# Trd_pcb.net
KiCad netlist of a schematic drawn in EAGLE
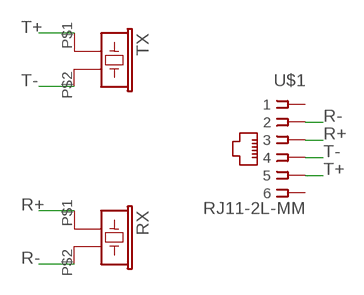
[diagram p0: schematic, sheet 1]

(export (version "E")
  (design (tool "Eeschema 10.0.6"))
  (components
    (comp (ref "RX")
      (value "400ST/R100")
      (footprint "eagle-import:DIA-9.7-5")
      (libsource (lib "eagle-import") (part "400ST/R100"))
    )
    (comp (ref "TX")
      (value "400ST/R100")
      (footprint "eagle-import:DIA-9.7-5")
      (libsource (lib "eagle-import") (part "400ST/R100"))
    )
    (comp (ref "U$1")
      (value "RJ11-2L-MM")
      (footprint "eagle-import:RJ11-NO_SHIELD_2")
      (libsource (lib "eagle-import") (part "RJ11-2L-MM"))
    )
  )
  (nets
    (net (code "1") (name "/R+") (class "Default")
      (node (ref "RX") (pin "P$1") (pinfunction "1_P$1") (pintype "passive"))
      (node (ref "U$1") (pin "3") (pinfunction "3_3") (pintype "passive"))
    )
    (net (code "2") (name "/R-") (class "Default")
      (node (ref "RX") (pin "P$2") (pinfunction "2_P$2") (pintype "passive"))
      (node (ref "U$1") (pin "2") (pinfunction "2_2") (pintype "passive"))
    )
    (net (code "3") (name "/T+") (class "Default")
      (node (ref "TX") (pin "P$1") (pinfunction "1_P$1") (pintype "passive"))
      (node (ref "U$1") (pin "5") (pinfunction "5_5") (pintype "passive"))
    )
    (net (code "4") (name "/T-") (class "Default")
      (node (ref "TX") (pin "P$2") (pinfunction "2_P$2") (pintype "passive"))
      (node (ref "U$1") (pin "4") (pinfunction "4_4") (pintype "passive"))
    )
    (net (code "5") (name "unconnected-(U$1-Pad1)") (class "Default")
      (node (ref "U$1") (pin "1") (pinfunction "1_1") (pintype "passive"))
    )
    (net (code "6") (name "unconnected-(U$1-Pad6)") (class "Default")
      (node (ref "U$1") (pin "6") (pinfunction "6_6") (pintype "passive"))
    )
  )
)
